# lodev-s76s.net
KiCad netlist of a schematic drawn in EAGLE
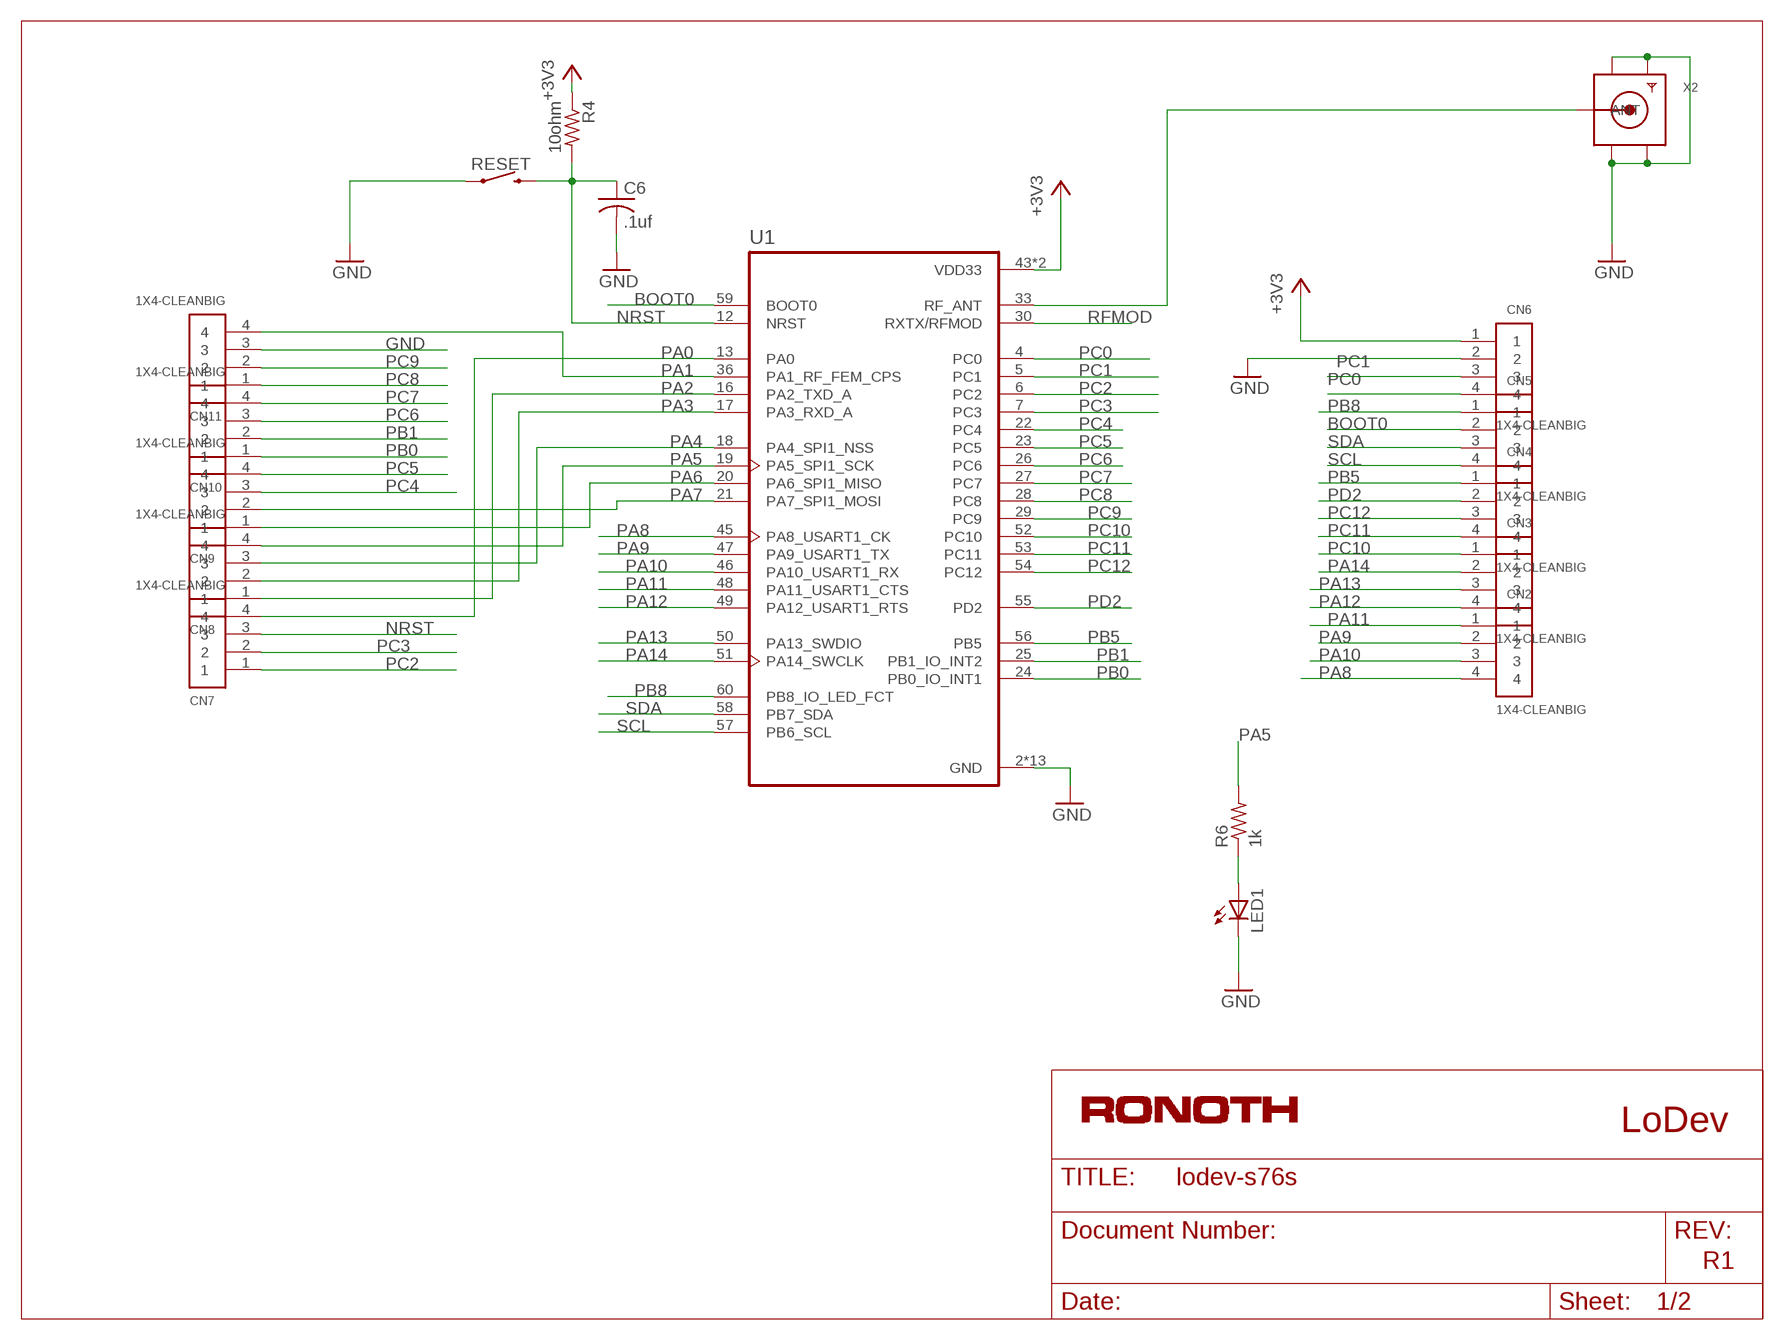
[diagram p0: schematic, sheet 1]
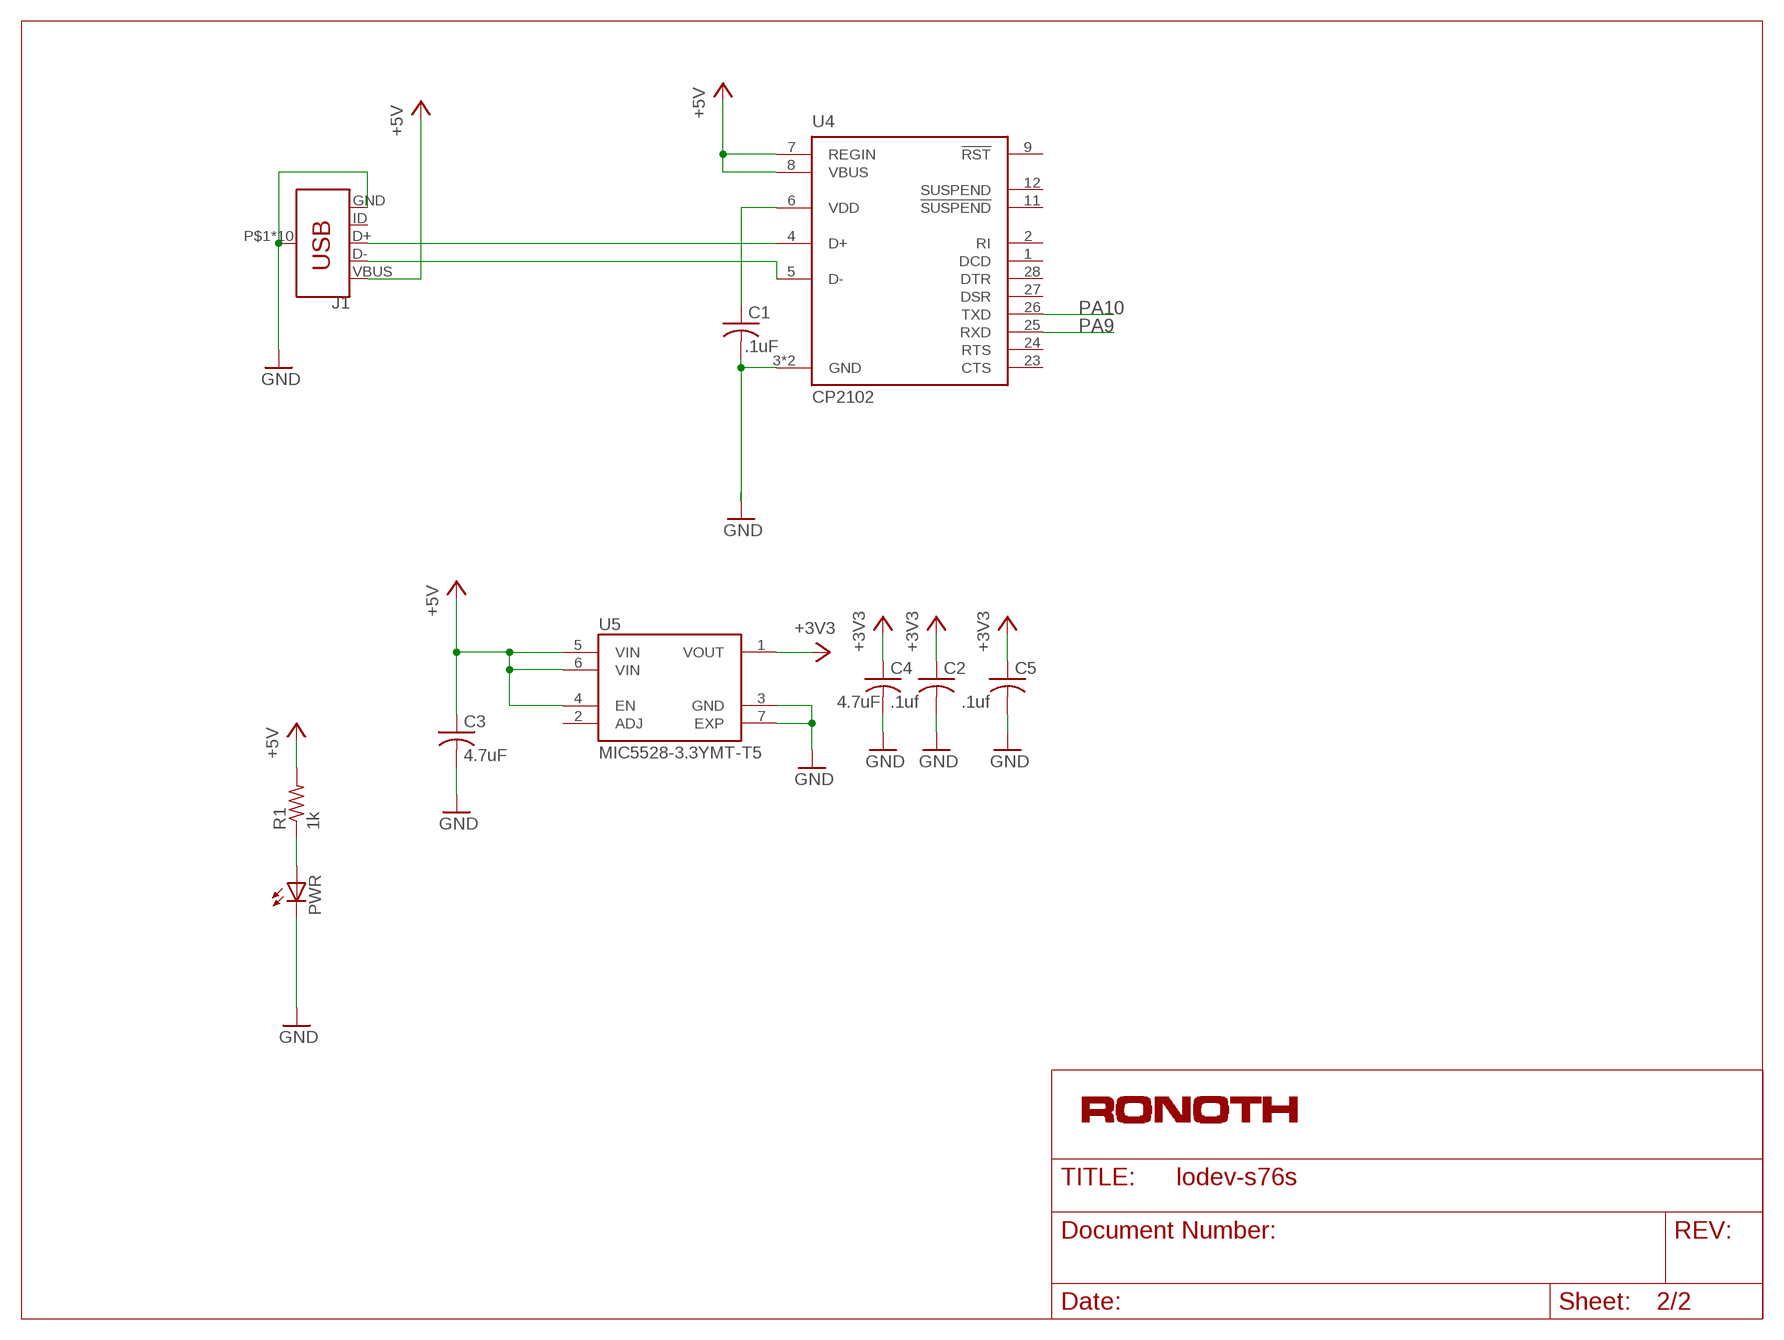
[diagram p1: schematic, sheet 2]

(export (version "E")
  (design (tool "Eeschema 10.0.6"))
  (components
    (comp (ref "C6")
      (value ".1uf")
      (footprint "eagle-import:C0603K")
      (libsource (lib "eagle-import") (part "C-USC0603K"))
    )
    (comp (ref "CN2")
      (value "1X4-CLEANBIG")
      (footprint "eagle-import:1X04-CLEANBIG")
      (libsource (lib "eagle-import") (part "1X4-CLEANBIG"))
    )
    (comp (ref "CN3")
      (value "1X4-CLEANBIG")
      (footprint "eagle-import:1X04-CLEANBIG")
      (libsource (lib "eagle-import") (part "1X4-CLEANBIG"))
    )
    (comp (ref "CN4")
      (value "1X4-CLEANBIG")
      (footprint "eagle-import:1X04-CLEANBIG")
      (libsource (lib "eagle-import") (part "1X4-CLEANBIG"))
    )
    (comp (ref "CN5")
      (value "1X4-CLEANBIG")
      (footprint "eagle-import:1X04-CLEANBIG")
      (libsource (lib "eagle-import") (part "1X4-CLEANBIG"))
    )
    (comp (ref "CN6")
      (value "1X4-CLEANBIG")
      (footprint "eagle-import:1X04-CLEANBIG")
      (libsource (lib "eagle-import") (part "1X4-CLEANBIG"))
    )
    (comp (ref "CN7")
      (value "1X4-CLEANBIG")
      (footprint "eagle-import:1X04-CLEANBIG")
      (libsource (lib "eagle-import") (part "1X4-CLEANBIG"))
    )
    (comp (ref "CN8")
      (value "1X4-CLEANBIG")
      (footprint "eagle-import:1X04-CLEANBIG")
      (libsource (lib "eagle-import") (part "1X4-CLEANBIG"))
    )
    (comp (ref "CN9")
      (value "1X4-CLEANBIG")
      (footprint "eagle-import:1X04-CLEANBIG")
      (libsource (lib "eagle-import") (part "1X4-CLEANBIG"))
    )
    (comp (ref "CN10")
      (value "1X4-CLEANBIG")
      (footprint "eagle-import:1X04-CLEANBIG")
      (libsource (lib "eagle-import") (part "1X4-CLEANBIG"))
    )
    (comp (ref "CN11")
      (value "1X4-CLEANBIG")
      (footprint "eagle-import:1X04-CLEANBIG")
      (libsource (lib "eagle-import") (part "1X4-CLEANBIG"))
    )
    (comp (ref "LED1")
      (value "LEDCHIPLED_0603")
      (footprint "eagle-import:CHIPLED_0603")
      (libsource (lib "eagle-import") (part "LEDCHIPLED_0603"))
    )
    (comp (ref "R4")
      (value "10ohm")
      (footprint "eagle-import:R0603")
      (libsource (lib "eagle-import") (part "R-US_R0603"))
    )
    (comp (ref "R6")
      (value "1k")
      (footprint "eagle-import:R0603")
      (libsource (lib "eagle-import") (part "R-US_R0603"))
    )
    (comp (ref "RESET")
      (value "MOMENTARY-SWITCH-SPST-SMD-6.0X3.5MM")
      (footprint "eagle-import:TACTILE_SWITCH_SMD_6.0X3.5MM")
      (libsource (lib "eagle-import") (part "MOMENTARY-SWITCH-SPST-SMD-6.0X3.5MM"))
    )
    (comp (ref "U1")
      (value "S76S")
      (footprint "eagle-import:ACSIP_S76S")
      (fields (field (name "MF") "AcSIP") (field (name "MP") "S76s"))
      (libsource (lib "eagle-import") (part "S76S"))
    )
    (comp (ref "X2")
      (value "SMACONNECTOR_EDGE")
      (footprint "eagle-import:SMA_EDGELAUNCH")
      (libsource (lib "eagle-import") (part "SMACONNECTOR_EDGE"))
    )
    (comp (ref "C1")
      (value ".1uF")
      (footprint "eagle-import:C0603K")
      (libsource (lib "eagle-import") (part "C-USC0603K"))
    )
    (comp (ref "C2")
      (value ".1uf")
      (footprint "eagle-import:C0603K")
      (libsource (lib "eagle-import") (part "C-USC0603K"))
    )
    (comp (ref "C3")
      (value "4.7uF")
      (footprint "eagle-import:C0603K")
      (libsource (lib "eagle-import") (part "C-USC0603K"))
    )
    (comp (ref "C4")
      (value "4.7uF")
      (footprint "eagle-import:C0603K")
      (libsource (lib "eagle-import") (part "C-USC0603K"))
    )
    (comp (ref "C5")
      (value ".1uf")
      (footprint "eagle-import:C0603K")
      (libsource (lib "eagle-import") (part "C-USC0603K"))
    )
    (comp (ref "J1")
      (value "USB_MICRO-B")
      (footprint "eagle-import:USB-MICROB-PTH")
      (libsource (lib "eagle-import") (part "USB_MICRO-B"))
    )
    (comp (ref "PWR")
      (value "LEDCHIPLED_0603")
      (footprint "eagle-import:CHIPLED_0603")
      (libsource (lib "eagle-import") (part "LEDCHIPLED_0603"))
    )
    (comp (ref "R1")
      (value "1k")
      (footprint "eagle-import:R0603")
      (libsource (lib "eagle-import") (part "R-US_R0603"))
    )
    (comp (ref "U4")
      (value "CP2102")
      (footprint "eagle-import:MLP28")
      (fields (field (name "MF") "FARNELL") (field (name "MPN") "CP2102-GM"))
      (libsource (lib "eagle-import") (part "CP2102"))
    )
    (comp (ref "U5")
      (value "MIC5528-3.3YMT-T5")
      (footprint "eagle-import:SON50P160X160X60-7N")
      (fields (field (name "MF") "Microchip") (field (name "MP") "MIC94325YMT-TR"))
      (libsource (lib "eagle-import") (part "MIC94325YMT-TR"))
    )
  )
  (nets
    (net (code "1") (name "+3V3") (class "Default")
      (node (ref "C2") (pin "1") (pinfunction "1_1") (pintype "passive"))
      (node (ref "C4") (pin "1") (pinfunction "1_1") (pintype "passive"))
      (node (ref "C5") (pin "1") (pinfunction "1_1") (pintype "passive"))
      (node (ref "CN6") (pin "1") (pinfunction "1_1") (pintype "bidirectional"))
      (node (ref "R4") (pin "1") (pinfunction "1_1") (pintype "passive"))
      (node (ref "U1") (pin "43") (pinfunction "VDD33_43") (pintype "power_in"))
      (node (ref "U1") (pin "44") (pinfunction "VDD33_44") (pintype "power_in"))
      (node (ref "U5") (pin "1") (pinfunction "VOUT_1") (pintype "output"))
    )
    (net (code "2") (name "+5V") (class "Default")
      (node (ref "C3") (pin "1") (pinfunction "1_1") (pintype "passive"))
      (node (ref "J1") (pin "VBUS") (pinfunction "VBUS_VBUS") (pintype "power_in"))
      (node (ref "R1") (pin "2") (pinfunction "2_2") (pintype "passive"))
      (node (ref "U4") (pin "7") (pinfunction "REGIN_7") (pintype "passive"))
      (node (ref "U4") (pin "8") (pinfunction "VBUS_8") (pintype "input"))
      (node (ref "U5") (pin "4") (pinfunction "EN_4") (pintype "input"))
      (node (ref "U5") (pin "5") (pinfunction "VIN_5") (pintype "input"))
      (node (ref "U5") (pin "6") (pinfunction "VIN_6") (pintype "input"))
    )
    (net (code "3") (name "BOOT0") (class "Default")
      (node (ref "CN5") (pin "2") (pinfunction "2_2") (pintype "bidirectional"))
      (node (ref "U1") (pin "59") (pinfunction "BOOT0_59") (pintype "input"))
    )
    (net (code "4") (name "GND") (class "Default")
      (node (ref "C1") (pin "2") (pinfunction "2_2") (pintype "passive"))
      (node (ref "C2") (pin "2") (pinfunction "2_2") (pintype "passive"))
      (node (ref "C3") (pin "2") (pinfunction "2_2") (pintype "passive"))
      (node (ref "C4") (pin "2") (pinfunction "2_2") (pintype "passive"))
      (node (ref "C5") (pin "2") (pinfunction "2_2") (pintype "passive"))
      (node (ref "C6") (pin "2") (pinfunction "2_2") (pintype "passive"))
      (node (ref "CN11") (pin "3") (pinfunction "3_3") (pintype "bidirectional"))
      (node (ref "CN6") (pin "2") (pinfunction "2_2") (pintype "bidirectional"))
      (node (ref "J1") (pin "GND") (pinfunction "GND_GND") (pintype "power_in"))
      (node (ref "J1") (pin "P$1") (pinfunction "SHIELD_P$1") (pintype "bidirectional"))
      (node (ref "J1") (pin "P$10") (pinfunction "SHIELD_P$10") (pintype "bidirectional"))
      (node (ref "J1") (pin "P$12") (pinfunction "SHIELD_P$12") (pintype "bidirectional"))
      (node (ref "J1") (pin "P$3") (pinfunction "SHIELD_P$3") (pintype "bidirectional"))
      (node (ref "J1") (pin "P$4") (pinfunction "SHIELD_P$4") (pintype "bidirectional"))
      (node (ref "J1") (pin "P$8") (pinfunction "SHIELD_P$8") (pintype "bidirectional"))
      (node (ref "J1") (pin "SHEILD2") (pinfunction "SHIELD_SHEILD2") (pintype "bidirectional"))
      (node (ref "J1") (pin "SHIELD") (pinfunction "SHIELD_SHIELD") (pintype "bidirectional"))
      (node (ref "J1") (pin "SHIELD3") (pinfunction "SHIELD_SHIELD3") (pintype "bidirectional"))
      (node (ref "J1") (pin "SHIELD4") (pinfunction "SHIELD_SHIELD4") (pintype "bidirectional"))
      (node (ref "LED1") (pin "C") (pinfunction "C_C") (pintype "passive"))
      (node (ref "PWR") (pin "C") (pinfunction "C_C") (pintype "passive"))
      (node (ref "RESET") (pin "1") (pinfunction "1_1") (pintype "passive"))
      (node (ref "U1") (pin "14") (pinfunction "GND_14") (pintype "power_in"))
      (node (ref "U1") (pin "15") (pinfunction "GND_15") (pintype "power_in"))
      (node (ref "U1") (pin "2") (pinfunction "GND_2") (pintype "power_in"))
      (node (ref "U1") (pin "3") (pinfunction "GND_3") (pintype "power_in"))
      (node (ref "U1") (pin "31") (pinfunction "GND_31") (pintype "power_in"))
      (node (ref "U1") (pin "32") (pinfunction "GND_32") (pintype "power_in"))
      (node (ref "U1") (pin "34") (pinfunction "GND_34") (pintype "power_in"))
      (node (ref "U1") (pin "35") (pinfunction "GND_35") (pintype "power_in"))
      (node (ref "U1") (pin "37") (pinfunction "GND_37") (pintype "power_in"))
      (node (ref "U1") (pin "39") (pinfunction "GND_39") (pintype "power_in"))
      (node (ref "U1") (pin "41") (pinfunction "GND_41") (pintype "power_in"))
      (node (ref "U1") (pin "61") (pinfunction "GND_61") (pintype "power_in"))
      (node (ref "U1") (pin "62") (pinfunction "GND_62") (pintype "power_in"))
      (node (ref "U4") (pin "3") (pinfunction "GND_3") (pintype "power_in"))
      (node (ref "U4") (pin "EXP") (pinfunction "GND_EXP") (pintype "power_in"))
      (node (ref "U5") (pin "3") (pinfunction "GND_3") (pintype "power_in"))
      (node (ref "U5") (pin "7") (pinfunction "EXP_7") (pintype "power_in"))
      (node (ref "X2") (pin "GND@1") (pinfunction "GND4_GND@1") (pintype "power_in"))
      (node (ref "X2") (pin "GND@2") (pinfunction "GND3_GND@2") (pintype "power_in"))
      (node (ref "X2") (pin "GND@3") (pinfunction "GND2_GND@3") (pintype "power_in"))
      (node (ref "X2") (pin "GND@4") (pinfunction "GND1_GND@4") (pintype "power_in"))
    )
    (net (code "5") (name "NRST") (class "Default")
      (node (ref "C6") (pin "1") (pinfunction "1_1") (pintype "passive"))
      (node (ref "CN7") (pin "3") (pinfunction "3_3") (pintype "bidirectional"))
      (node (ref "R4") (pin "2") (pinfunction "2_2") (pintype "passive"))
      (node (ref "RESET") (pin "2") (pinfunction "2_2") (pintype "passive"))
      (node (ref "U1") (pin "12") (pinfunction "NRST_12") (pintype "bidirectional"))
    )
    (net (code "6") (name "Net-(LED1-PadA)") (class "Default")
      (node (ref "LED1") (pin "A") (pinfunction "A_A") (pintype "passive"))
      (node (ref "R6") (pin "1") (pinfunction "1_1") (pintype "passive"))
    )
    (net (code "7") (name "Net-(PWR-PadA)") (class "Default")
      (node (ref "PWR") (pin "A") (pinfunction "A_A") (pintype "passive"))
      (node (ref "R1") (pin "1") (pinfunction "1_1") (pintype "passive"))
    )
    (net (code "8") (name "Net-(U1-RF_ANT)") (class "Default")
      (node (ref "U1") (pin "33") (pinfunction "RF_ANT_33") (pintype "bidirectional"))
      (node (ref "X2") (pin "P") (pinfunction "ANT_P") (pintype "bidirectional"))
    )
    (net (code "9") (name "Net-(U4-D+)") (class "Default")
      (node (ref "J1") (pin "D+") (pinfunction "D+_D+") (pintype "bidirectional"))
      (node (ref "U4") (pin "4") (pinfunction "D+_4") (pintype "bidirectional"))
    )
    (net (code "10") (name "Net-(U4-D-)") (class "Default")
      (node (ref "J1") (pin "D-") (pinfunction "D-_D-") (pintype "bidirectional"))
      (node (ref "U4") (pin "5") (pinfunction "D-_5") (pintype "bidirectional"))
    )
    (net (code "11") (name "Net-(U4-VDD)") (class "Default")
      (node (ref "C1") (pin "1") (pinfunction "1_1") (pintype "passive"))
      (node (ref "U4") (pin "6") (pinfunction "VDD_6") (pintype "power_in"))
    )
    (net (code "12") (name "PA0") (class "Default")
      (node (ref "CN7") (pin "4") (pinfunction "4_4") (pintype "bidirectional"))
      (node (ref "U1") (pin "13") (pinfunction "PA0_13") (pintype "bidirectional"))
    )
    (net (code "13") (name "PA1") (class "Default")
      (node (ref "CN11") (pin "4") (pinfunction "4_4") (pintype "bidirectional"))
      (node (ref "U1") (pin "36") (pinfunction "PA1_RF_FEM_CPS_36") (pintype "bidirectional"))
    )
    (net (code "14") (name "PA2") (class "Default")
      (node (ref "CN8") (pin "1") (pinfunction "1_1") (pintype "bidirectional"))
      (node (ref "U1") (pin "16") (pinfunction "PA2_TXD_A_16") (pintype "bidirectional"))
    )
    (net (code "15") (name "PA3") (class "Default")
      (node (ref "CN8") (pin "2") (pinfunction "2_2") (pintype "bidirectional"))
      (node (ref "U1") (pin "17") (pinfunction "PA3_RXD_A_17") (pintype "bidirectional"))
    )
    (net (code "16") (name "PA4") (class "Default")
      (node (ref "CN8") (pin "3") (pinfunction "3_3") (pintype "bidirectional"))
      (node (ref "U1") (pin "18") (pinfunction "PA4_SPI1_NSS_18") (pintype "bidirectional"))
    )
    (net (code "17") (name "PA5") (class "Default")
      (node (ref "CN8") (pin "4") (pinfunction "4_4") (pintype "bidirectional"))
      (node (ref "R6") (pin "2") (pinfunction "2_2") (pintype "passive"))
      (node (ref "U1") (pin "19") (pinfunction "PA5_SPI1_SCK_19") (pintype "bidirectional"))
    )
    (net (code "18") (name "PA6") (class "Default")
      (node (ref "CN9") (pin "1") (pinfunction "1_1") (pintype "bidirectional"))
      (node (ref "U1") (pin "20") (pinfunction "PA6_SPI1_MISO_20") (pintype "bidirectional"))
    )
    (net (code "19") (name "PA7") (class "Default")
      (node (ref "CN9") (pin "2") (pinfunction "2_2") (pintype "bidirectional"))
      (node (ref "U1") (pin "21") (pinfunction "PA7_SPI1_MOSI_21") (pintype "bidirectional"))
    )
    (net (code "20") (name "PA8") (class "Default")
      (node (ref "CN2") (pin "4") (pinfunction "4_4") (pintype "bidirectional"))
      (node (ref "U1") (pin "45") (pinfunction "PA8_USART1_CK_45") (pintype "bidirectional"))
    )
    (net (code "21") (name "PA9") (class "Default")
      (node (ref "CN2") (pin "2") (pinfunction "2_2") (pintype "bidirectional"))
      (node (ref "U1") (pin "47") (pinfunction "PA9_USART1_TX_47") (pintype "bidirectional"))
      (node (ref "U4") (pin "25") (pinfunction "RXD_25") (pintype "input"))
    )
    (net (code "22") (name "PA10") (class "Default")
      (node (ref "CN2") (pin "3") (pinfunction "3_3") (pintype "bidirectional"))
      (node (ref "U1") (pin "46") (pinfunction "PA10_USART1_RX_46") (pintype "bidirectional"))
      (node (ref "U4") (pin "26") (pinfunction "TXD_26") (pintype "output"))
    )
    (net (code "23") (name "PA11") (class "Default")
      (node (ref "CN2") (pin "1") (pinfunction "1_1") (pintype "bidirectional"))
      (node (ref "U1") (pin "48") (pinfunction "PA11_USART1_CTS_48") (pintype "bidirectional"))
    )
    (net (code "24") (name "PA12") (class "Default")
      (node (ref "CN3") (pin "4") (pinfunction "4_4") (pintype "bidirectional"))
      (node (ref "U1") (pin "49") (pinfunction "PA12_USART1_RTS_49") (pintype "bidirectional"))
    )
    (net (code "25") (name "PA13") (class "Default")
      (node (ref "CN3") (pin "3") (pinfunction "3_3") (pintype "bidirectional"))
      (node (ref "U1") (pin "50") (pinfunction "PA13_SWDIO_50") (pintype "bidirectional"))
    )
    (net (code "26") (name "PA14") (class "Default")
      (node (ref "CN3") (pin "2") (pinfunction "2_2") (pintype "bidirectional"))
      (node (ref "U1") (pin "51") (pinfunction "PA14_SWCLK_51") (pintype "bidirectional"))
    )
    (net (code "27") (name "PB0") (class "Default")
      (node (ref "CN10") (pin "1") (pinfunction "1_1") (pintype "bidirectional"))
      (node (ref "U1") (pin "24") (pinfunction "PB0_IO_INT1_24") (pintype "bidirectional"))
    )
    (net (code "28") (name "PB1") (class "Default")
      (node (ref "CN10") (pin "2") (pinfunction "2_2") (pintype "bidirectional"))
      (node (ref "U1") (pin "25") (pinfunction "PB1_IO_INT2_25") (pintype "bidirectional"))
    )
    (net (code "29") (name "PB5") (class "Default")
      (node (ref "CN4") (pin "1") (pinfunction "1_1") (pintype "bidirectional"))
      (node (ref "U1") (pin "56") (pinfunction "PB5_56") (pintype "bidirectional"))
    )
    (net (code "30") (name "PB8") (class "Default")
      (node (ref "CN5") (pin "1") (pinfunction "1_1") (pintype "bidirectional"))
      (node (ref "U1") (pin "60") (pinfunction "PB8_IO_LED_FCT_60") (pintype "bidirectional"))
    )
    (net (code "31") (name "PC0") (class "Default")
      (node (ref "CN6") (pin "4") (pinfunction "4_4") (pintype "bidirectional"))
      (node (ref "U1") (pin "4") (pinfunction "PC0_4") (pintype "bidirectional"))
    )
    (net (code "32") (name "PC1") (class "Default")
      (node (ref "CN6") (pin "3") (pinfunction "3_3") (pintype "bidirectional"))
      (node (ref "U1") (pin "5") (pinfunction "PC1_5") (pintype "bidirectional"))
    )
    (net (code "33") (name "PC2") (class "Default")
      (node (ref "CN7") (pin "1") (pinfunction "1_1") (pintype "bidirectional"))
      (node (ref "U1") (pin "6") (pinfunction "PC2_6") (pintype "bidirectional"))
    )
    (net (code "34") (name "PC3") (class "Default")
      (node (ref "CN7") (pin "2") (pinfunction "2_2") (pintype "bidirectional"))
      (node (ref "U1") (pin "7") (pinfunction "PC3_7") (pintype "bidirectional"))
    )
    (net (code "35") (name "PC4") (class "Default")
      (node (ref "CN9") (pin "3") (pinfunction "3_3") (pintype "bidirectional"))
      (node (ref "U1") (pin "22") (pinfunction "PC4_22") (pintype "bidirectional"))
    )
    (net (code "36") (name "PC5") (class "Default")
      (node (ref "CN9") (pin "4") (pinfunction "4_4") (pintype "bidirectional"))
      (node (ref "U1") (pin "23") (pinfunction "PC5_23") (pintype "bidirectional"))
    )
    (net (code "37") (name "PC6") (class "Default")
      (node (ref "CN10") (pin "3") (pinfunction "3_3") (pintype "bidirectional"))
      (node (ref "U1") (pin "26") (pinfunction "PC6_26") (pintype "bidirectional"))
    )
    (net (code "38") (name "PC7") (class "Default")
      (node (ref "CN10") (pin "4") (pinfunction "4_4") (pintype "bidirectional"))
      (node (ref "U1") (pin "27") (pinfunction "PC7_27") (pintype "bidirectional"))
    )
    (net (code "39") (name "PC8") (class "Default")
      (node (ref "CN11") (pin "1") (pinfunction "1_1") (pintype "bidirectional"))
      (node (ref "U1") (pin "28") (pinfunction "PC8_28") (pintype "bidirectional"))
    )
    (net (code "40") (name "PC9") (class "Default")
      (node (ref "CN11") (pin "2") (pinfunction "2_2") (pintype "bidirectional"))
      (node (ref "U1") (pin "29") (pinfunction "PC9_29") (pintype "bidirectional"))
    )
    (net (code "41") (name "PC10") (class "Default")
      (node (ref "CN3") (pin "1") (pinfunction "1_1") (pintype "bidirectional"))
      (node (ref "U1") (pin "52") (pinfunction "PC10_52") (pintype "bidirectional"))
    )
    (net (code "42") (name "PC11") (class "Default")
      (node (ref "CN4") (pin "4") (pinfunction "4_4") (pintype "bidirectional"))
      (node (ref "U1") (pin "53") (pinfunction "PC11_53") (pintype "bidirectional"))
    )
    (net (code "43") (name "PC12") (class "Default")
      (node (ref "CN4") (pin "3") (pinfunction "3_3") (pintype "bidirectional"))
      (node (ref "U1") (pin "54") (pinfunction "PC12_54") (pintype "bidirectional"))
    )
    (net (code "44") (name "PD2") (class "Default")
      (node (ref "CN4") (pin "2") (pinfunction "2_2") (pintype "bidirectional"))
      (node (ref "U1") (pin "55") (pinfunction "PD2_55") (pintype "bidirectional"))
    )
    (net (code "45") (name "RFMOD") (class "Default")
      (node (ref "U1") (pin "30") (pinfunction "RXTX/RFMOD_30") (pintype "output"))
    )
    (net (code "46") (name "SCL") (class "Default")
      (node (ref "CN5") (pin "4") (pinfunction "4_4") (pintype "bidirectional"))
      (node (ref "U1") (pin "57") (pinfunction "PB6_SCL_57") (pintype "bidirectional"))
    )
    (net (code "47") (name "SDA") (class "Default")
      (node (ref "CN5") (pin "3") (pinfunction "3_3") (pintype "bidirectional"))
      (node (ref "U1") (pin "58") (pinfunction "PB7_SDA_58") (pintype "bidirectional"))
    )
    (net (code "48") (name "unconnected-(J1-PadID)") (class "Default")
      (node (ref "J1") (pin "ID") (pinfunction "ID_ID") (pintype "bidirectional"))
    )
    (net (code "49") (name "unconnected-(U4-CTS-Pad23)") (class "Default")
      (node (ref "U4") (pin "23") (pinfunction "CTS_23") (pintype "input"))
    )
    (net (code "50") (name "unconnected-(U4-DCD-Pad1)") (class "Default")
      (node (ref "U4") (pin "1") (pinfunction "DCD_1") (pintype "input"))
    )
    (net (code "51") (name "unconnected-(U4-DSR-Pad27)") (class "Default")
      (node (ref "U4") (pin "27") (pinfunction "DSR_27") (pintype "input"))
    )
    (net (code "52") (name "unconnected-(U4-DTR-Pad28)") (class "Default")
      (node (ref "U4") (pin "28") (pinfunction "DTR_28") (pintype "output"))
    )
    (net (code "53") (name "unconnected-(U4-RI-Pad2)") (class "Default")
      (node (ref "U4") (pin "2") (pinfunction "RI_2") (pintype "input"))
    )
    (net (code "54") (name "unconnected-(U4-RTS-Pad24)") (class "Default")
      (node (ref "U4") (pin "24") (pinfunction "RTS_24") (pintype "output"))
    )
    (net (code "55") (name "unconnected-(U4-SUSPEND-Pad12)") (class "Default")
      (node (ref "U4") (pin "12") (pinfunction "SUSPEND_12") (pintype "output"))
    )
    (net (code "56") (name "unconnected-(U4-~{RST}-Pad9)") (class "Default")
      (node (ref "U4") (pin "9") (pinfunction "~{RST}_9") (pintype "bidirectional"))
    )
    (net (code "57") (name "unconnected-(U4-~{SUSPEND}-Pad11)") (class "Default")
      (node (ref "U4") (pin "11") (pinfunction "~{SUSPEND}_11") (pintype "output"))
    )
    (net (code "58") (name "unconnected-(U5-ADJ-Pad2)") (class "Default")
      (node (ref "U5") (pin "2") (pinfunction "ADJ_2") (pintype "passive"))
    )
  )
)
